# Tracksoar_v2_shield_template.net
KiCad netlist of a schematic drawn in EAGLE
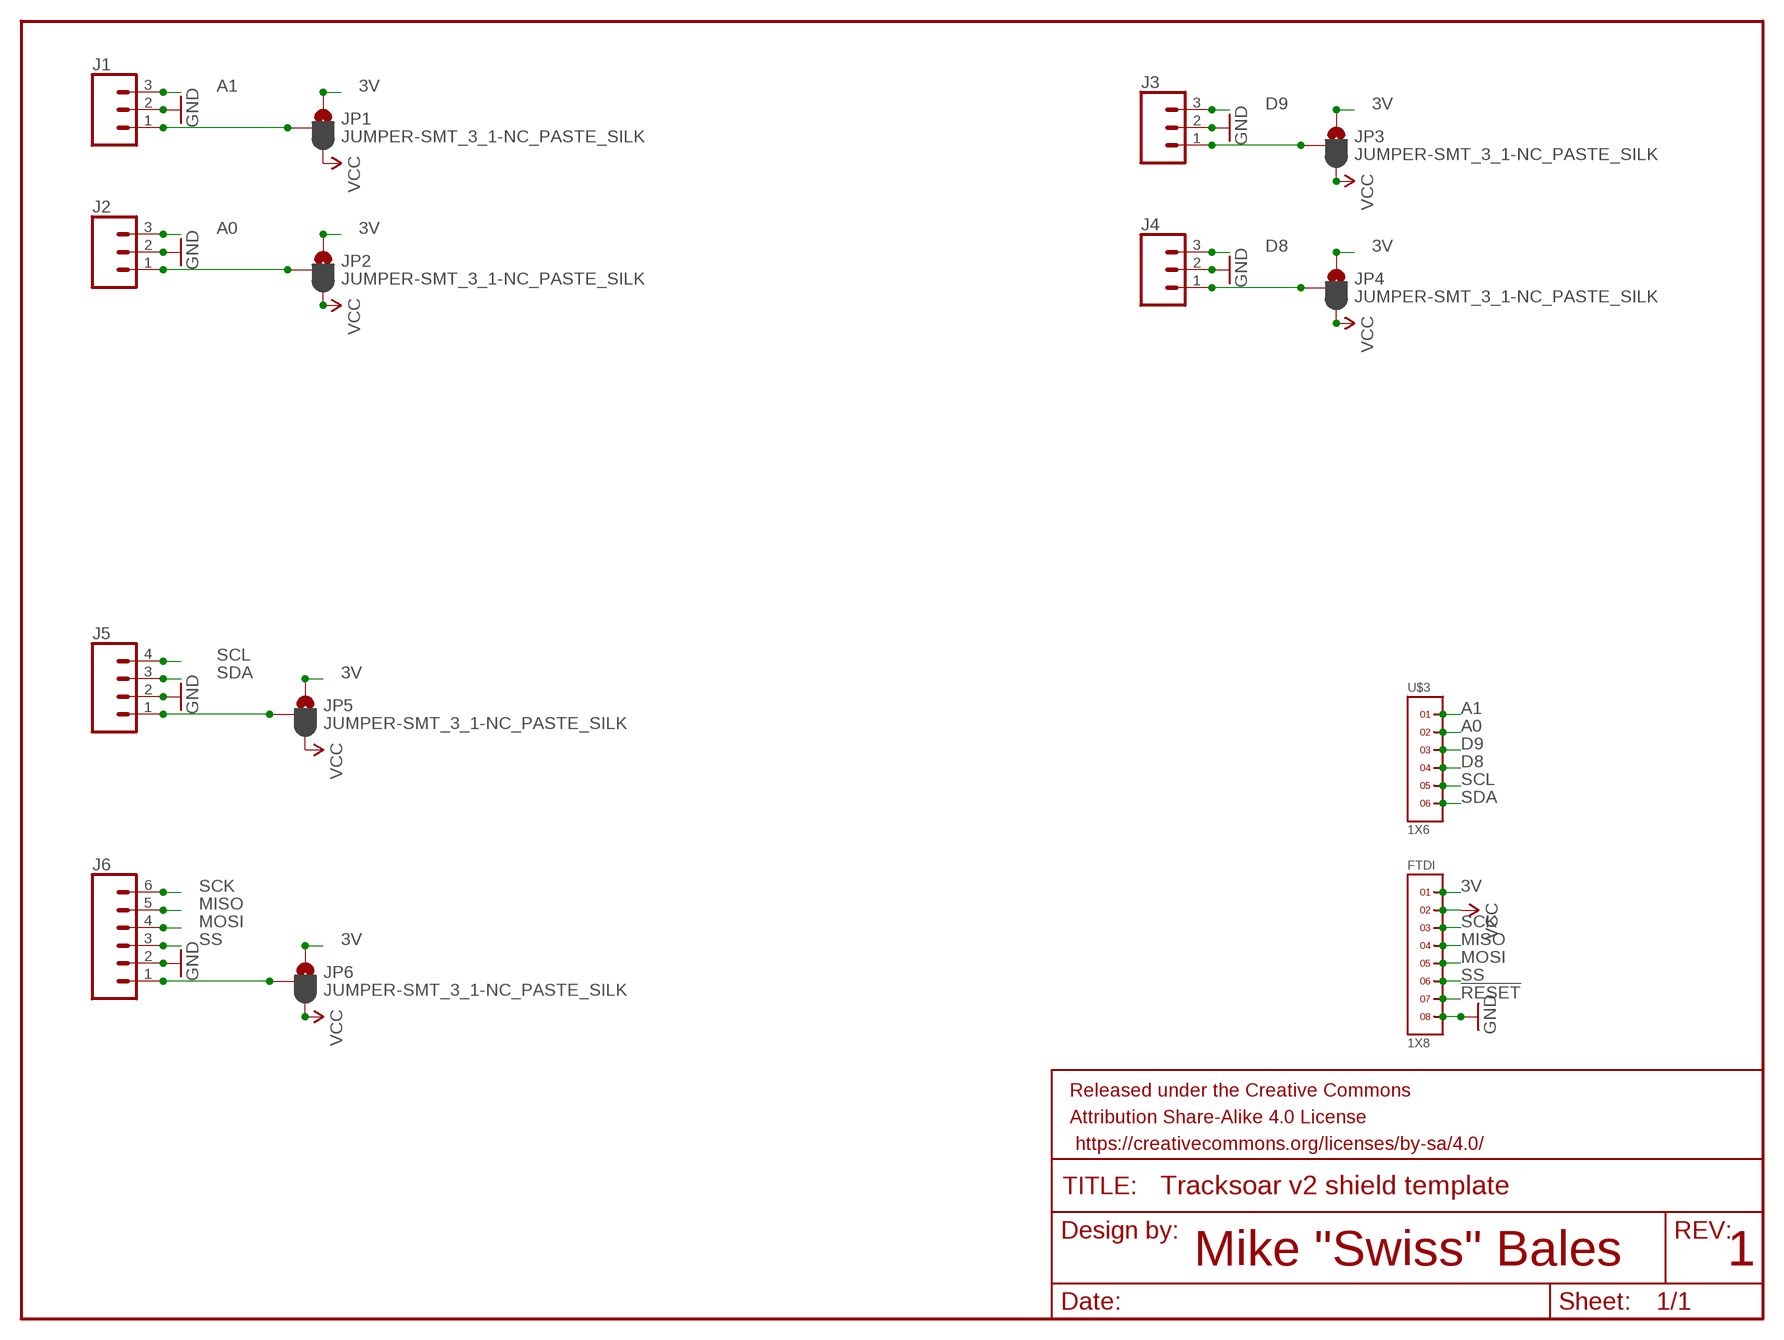
[diagram p0: schematic, sheet 1]

(export (version "E")
  (design (tool "Eeschema 10.0.6"))
  (components
    (comp (ref "FRAME1")
      (value "FRAME-LETTER")
      (footprint "eagle-import:CREATIVE_COMMONS")
      (libsource (lib "eagle-import") (part "FRAME-LETTER"))
    )
    (comp (ref "FTDI")
      (value "1X8")
      (footprint "eagle-import:1X8")
      (libsource (lib "eagle-import") (part "1X8"))
    )
    (comp (ref "J1")
      (value "CONN_03LONGPADS")
      (footprint "eagle-import:1X03_LONGPADS")
      (libsource (lib "eagle-import") (part "CONN_03LONGPADS"))
    )
    (comp (ref "J2")
      (value "CONN_03LONGPADS")
      (footprint "eagle-import:1X03_LONGPADS")
      (libsource (lib "eagle-import") (part "CONN_03LONGPADS"))
    )
    (comp (ref "J3")
      (value "CONN_03LONGPADS")
      (footprint "eagle-import:1X03_LONGPADS")
      (libsource (lib "eagle-import") (part "CONN_03LONGPADS"))
    )
    (comp (ref "J4")
      (value "CONN_03LONGPADS")
      (footprint "eagle-import:1X03_LONGPADS")
      (libsource (lib "eagle-import") (part "CONN_03LONGPADS"))
    )
    (comp (ref "J5")
      (value "CONN_04LONGPADS")
      (footprint "eagle-import:1X04_LONGPADS")
      (libsource (lib "eagle-import") (part "CONN_04LONGPADS"))
    )
    (comp (ref "J6")
      (value "CONN_06LONGPADS")
      (footprint "eagle-import:1X06_LONGPADS")
      (libsource (lib "eagle-import") (part "CONN_06LONGPADS"))
    )
    (comp (ref "JP1")
      (value "JUMPER-SMT_3_1-NC_PASTE_SILK")
      (footprint "eagle-import:SMT-JUMPER_3_1-NC_PASTE_SILK")
      (libsource (lib "eagle-import") (part "JUMPER-SMT_3_1-NC_PASTE_SILK"))
    )
    (comp (ref "JP2")
      (value "JUMPER-SMT_3_1-NC_PASTE_SILK")
      (footprint "eagle-import:SMT-JUMPER_3_1-NC_PASTE_SILK")
      (libsource (lib "eagle-import") (part "JUMPER-SMT_3_1-NC_PASTE_SILK"))
    )
    (comp (ref "JP3")
      (value "JUMPER-SMT_3_1-NC_PASTE_SILK")
      (footprint "eagle-import:SMT-JUMPER_3_1-NC_PASTE_SILK")
      (libsource (lib "eagle-import") (part "JUMPER-SMT_3_1-NC_PASTE_SILK"))
    )
    (comp (ref "JP4")
      (value "JUMPER-SMT_3_1-NC_PASTE_SILK")
      (footprint "eagle-import:SMT-JUMPER_3_1-NC_PASTE_SILK")
      (libsource (lib "eagle-import") (part "JUMPER-SMT_3_1-NC_PASTE_SILK"))
    )
    (comp (ref "JP5")
      (value "JUMPER-SMT_3_1-NC_PASTE_SILK")
      (footprint "eagle-import:SMT-JUMPER_3_1-NC_PASTE_SILK")
      (libsource (lib "eagle-import") (part "JUMPER-SMT_3_1-NC_PASTE_SILK"))
    )
    (comp (ref "JP6")
      (value "JUMPER-SMT_3_1-NC_PASTE_SILK")
      (footprint "eagle-import:SMT-JUMPER_3_1-NC_PASTE_SILK")
      (libsource (lib "eagle-import") (part "JUMPER-SMT_3_1-NC_PASTE_SILK"))
    )
    (comp (ref "U$3")
      (value "1X6")
      (footprint "eagle-import:1X6")
      (libsource (lib "eagle-import") (part "1X6"))
    )
  )
  (nets
    (net (code "1") (name "/3V") (class "Default")
      (node (ref "FTDI") (pin "1") (pinfunction "1_1") (pintype "bidirectional"))
      (node (ref "JP1") (pin "1") (pinfunction "1_1") (pintype "passive"))
      (node (ref "JP2") (pin "1") (pinfunction "1_1") (pintype "passive"))
      (node (ref "JP3") (pin "1") (pinfunction "1_1") (pintype "passive"))
      (node (ref "JP4") (pin "1") (pinfunction "1_1") (pintype "passive"))
      (node (ref "JP5") (pin "1") (pinfunction "1_1") (pintype "passive"))
      (node (ref "JP6") (pin "1") (pinfunction "1_1") (pintype "passive"))
    )
    (net (code "2") (name "/A0") (class "Default")
      (node (ref "J2") (pin "3") (pinfunction "3_3") (pintype "passive"))
      (node (ref "U$3") (pin "2") (pinfunction "2_2") (pintype "bidirectional"))
    )
    (net (code "3") (name "/A1") (class "Default")
      (node (ref "J1") (pin "3") (pinfunction "3_3") (pintype "passive"))
      (node (ref "U$3") (pin "1") (pinfunction "1_1") (pintype "bidirectional"))
    )
    (net (code "4") (name "/D8") (class "Default")
      (node (ref "J4") (pin "3") (pinfunction "3_3") (pintype "passive"))
      (node (ref "U$3") (pin "4") (pinfunction "4_4") (pintype "bidirectional"))
    )
    (net (code "5") (name "/D9") (class "Default")
      (node (ref "J3") (pin "3") (pinfunction "3_3") (pintype "passive"))
      (node (ref "U$3") (pin "3") (pinfunction "3_3") (pintype "bidirectional"))
    )
    (net (code "6") (name "/MISO") (class "Default")
      (node (ref "FTDI") (pin "4") (pinfunction "4_4") (pintype "bidirectional"))
      (node (ref "J6") (pin "5") (pinfunction "5_5") (pintype "passive"))
    )
    (net (code "7") (name "/MOSI") (class "Default")
      (node (ref "FTDI") (pin "5") (pinfunction "5_5") (pintype "bidirectional"))
      (node (ref "J6") (pin "4") (pinfunction "4_4") (pintype "passive"))
    )
    (net (code "8") (name "/SCK") (class "Default")
      (node (ref "FTDI") (pin "3") (pinfunction "3_3") (pintype "bidirectional"))
      (node (ref "J6") (pin "6") (pinfunction "6_6") (pintype "passive"))
    )
    (net (code "9") (name "/SCL") (class "Default")
      (node (ref "J5") (pin "4") (pinfunction "4_4") (pintype "passive"))
      (node (ref "U$3") (pin "5") (pinfunction "5_5") (pintype "bidirectional"))
    )
    (net (code "10") (name "/SDA") (class "Default")
      (node (ref "J5") (pin "3") (pinfunction "3_3") (pintype "passive"))
      (node (ref "U$3") (pin "6") (pinfunction "6_6") (pintype "bidirectional"))
    )
    (net (code "11") (name "/SS") (class "Default")
      (node (ref "FTDI") (pin "6") (pinfunction "6_6") (pintype "bidirectional"))
      (node (ref "J6") (pin "3") (pinfunction "3_3") (pintype "passive"))
    )
    (net (code "12") (name "/~{RESET}") (class "Default")
      (node (ref "FTDI") (pin "7") (pinfunction "7_7") (pintype "bidirectional"))
    )
    (net (code "13") (name "GND") (class "Default")
      (node (ref "FTDI") (pin "8") (pinfunction "8_8") (pintype "bidirectional"))
      (node (ref "J1") (pin "2") (pinfunction "2_2") (pintype "passive"))
      (node (ref "J2") (pin "2") (pinfunction "2_2") (pintype "passive"))
      (node (ref "J3") (pin "2") (pinfunction "2_2") (pintype "passive"))
      (node (ref "J4") (pin "2") (pinfunction "2_2") (pintype "passive"))
      (node (ref "J5") (pin "2") (pinfunction "2_2") (pintype "passive"))
      (node (ref "J6") (pin "2") (pinfunction "2_2") (pintype "passive"))
    )
    (net (code "14") (name "Net-(J1-Pad1)") (class "Default")
      (node (ref "J1") (pin "1") (pinfunction "1_1") (pintype "passive"))
      (node (ref "JP1") (pin "2") (pinfunction "2_2") (pintype "passive"))
    )
    (net (code "15") (name "Net-(J2-Pad1)") (class "Default")
      (node (ref "J2") (pin "1") (pinfunction "1_1") (pintype "passive"))
      (node (ref "JP2") (pin "2") (pinfunction "2_2") (pintype "passive"))
    )
    (net (code "16") (name "Net-(J3-Pad1)") (class "Default")
      (node (ref "J3") (pin "1") (pinfunction "1_1") (pintype "passive"))
      (node (ref "JP3") (pin "2") (pinfunction "2_2") (pintype "passive"))
    )
    (net (code "17") (name "Net-(J4-Pad1)") (class "Default")
      (node (ref "J4") (pin "1") (pinfunction "1_1") (pintype "passive"))
      (node (ref "JP4") (pin "2") (pinfunction "2_2") (pintype "passive"))
    )
    (net (code "18") (name "Net-(J5-Pad1)") (class "Default")
      (node (ref "J5") (pin "1") (pinfunction "1_1") (pintype "passive"))
      (node (ref "JP5") (pin "2") (pinfunction "2_2") (pintype "passive"))
    )
    (net (code "19") (name "Net-(J6-Pad1)") (class "Default")
      (node (ref "J6") (pin "1") (pinfunction "1_1") (pintype "passive"))
      (node (ref "JP6") (pin "2") (pinfunction "2_2") (pintype "passive"))
    )
    (net (code "20") (name "VCC") (class "Default")
      (node (ref "FTDI") (pin "2") (pinfunction "2_2") (pintype "bidirectional"))
      (node (ref "JP1") (pin "3") (pinfunction "3_3") (pintype "passive"))
      (node (ref "JP2") (pin "3") (pinfunction "3_3") (pintype "passive"))
      (node (ref "JP3") (pin "3") (pinfunction "3_3") (pintype "passive"))
      (node (ref "JP4") (pin "3") (pinfunction "3_3") (pintype "passive"))
      (node (ref "JP5") (pin "3") (pinfunction "3_3") (pintype "passive"))
      (node (ref "JP6") (pin "3") (pinfunction "3_3") (pintype "passive"))
    )
  )
)
